# FT231X_Module.net
KiCad netlist of a schematic drawn in EAGLE
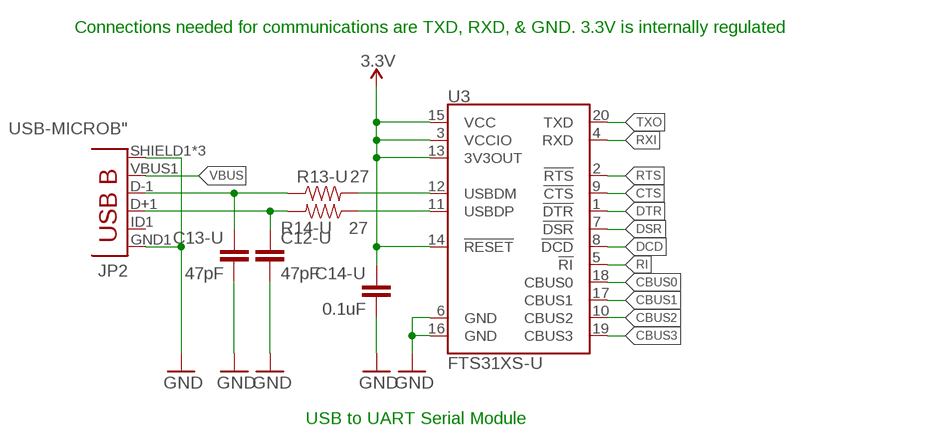
[diagram p0: schematic, sheet 1]

(export (version "E")
  (design (tool "Eeschema 10.0.6"))
  (components
    (comp (ref "C12-U")
      (value "47pF")
      (footprint "eagle-import:0603-CAP")
      (libsource (lib "eagle-import") (part "47PF-50V-5%(0603)"))
    )
    (comp (ref "C13-U")
      (value "47pF")
      (footprint "eagle-import:0603-CAP")
      (libsource (lib "eagle-import") (part "47PF-50V-5%(0603)"))
    )
    (comp (ref "C14-U")
      (value "0.1uF")
      (footprint "eagle-import:0603-CAP")
      (libsource (lib "eagle-import") (part "0.1UF-25V(+80/-20%)(0603)"))
    )
    (comp (ref "JP2")
      (value "USB-MICROB\"")
      (footprint "eagle-import:USB-B-MICRO-SMD_V03")
      (libsource (lib "eagle-import") (part "USB-MICROB{dblquote}"))
    )
    (comp (ref "R13-U")
      (value "27")
      (footprint "eagle-import:0603-RES")
      (libsource (lib "eagle-import") (part "27OHM1/10W1%(0603)0603-RES"))
    )
    (comp (ref "R14-U")
      (value "27")
      (footprint "eagle-import:0603-RES")
      (libsource (lib "eagle-import") (part "27OHM1/10W1%(0603)0603-RES"))
    )
    (comp (ref "U3")
      (value "FTS31XS-U")
      (footprint "eagle-import:SSOP20_L")
      (libsource (lib "eagle-import") (part "FT231XS"))
    )
  )
  (nets
    (net (code "1") (name "3.3V") (class "Default")
      (node (ref "C14-U") (pin "1") (pinfunction "1_1") (pintype "passive"))
      (node (ref "U3") (pin "13") (pinfunction "3V3OUT_13") (pintype "bidirectional"))
      (node (ref "U3") (pin "14") (pinfunction "~{RESET}_14") (pintype "bidirectional"))
      (node (ref "U3") (pin "15") (pinfunction "VCC_15") (pintype "bidirectional"))
      (node (ref "U3") (pin "3") (pinfunction "VCCIO_3") (pintype "bidirectional"))
    )
    (net (code "2") (name "CBUS0") (class "Default")
      (node (ref "U3") (pin "18") (pinfunction "CBUS0_18") (pintype "bidirectional"))
    )
    (net (code "3") (name "CBUS1") (class "Default")
      (node (ref "U3") (pin "17") (pinfunction "CBUS1_17") (pintype "bidirectional"))
    )
    (net (code "4") (name "CBUS2") (class "Default")
      (node (ref "U3") (pin "10") (pinfunction "CBUS2_10") (pintype "bidirectional"))
    )
    (net (code "5") (name "CBUS3") (class "Default")
      (node (ref "U3") (pin "19") (pinfunction "CBUS3_19") (pintype "bidirectional"))
    )
    (net (code "6") (name "CTS") (class "Default")
      (node (ref "U3") (pin "9") (pinfunction "~{CTS}_9") (pintype "bidirectional"))
    )
    (net (code "7") (name "DCD") (class "Default")
      (node (ref "U3") (pin "8") (pinfunction "~{DCD}_8") (pintype "bidirectional"))
    )
    (net (code "8") (name "DSR") (class "Default")
      (node (ref "U3") (pin "7") (pinfunction "~{DSR}_7") (pintype "bidirectional"))
    )
    (net (code "9") (name "DTR") (class "Default")
      (node (ref "U3") (pin "1") (pinfunction "~{DTR}_1") (pintype "bidirectional"))
    )
    (net (code "10") (name "GND") (class "Default")
      (node (ref "C12-U") (pin "2") (pinfunction "2_2") (pintype "passive"))
      (node (ref "C13-U") (pin "2") (pinfunction "2_2") (pintype "passive"))
      (node (ref "C14-U") (pin "2") (pinfunction "2_2") (pintype "passive"))
      (node (ref "JP2") (pin "GND1") (pinfunction "GND_GND1") (pintype "bidirectional"))
      (node (ref "JP2") (pin "SHIELD1") (pinfunction "SHIELD_SHIELD1") (pintype "bidirectional"))
      (node (ref "JP2") (pin "SHIELD2") (pinfunction "SHIELD_SHIELD2") (pintype "bidirectional"))
      (node (ref "JP2") (pin "SHIELD3") (pinfunction "SHIELD_SHIELD3") (pintype "bidirectional"))
      (node (ref "U3") (pin "16") (pinfunction "GND_16") (pintype "bidirectional"))
      (node (ref "U3") (pin "6") (pinfunction "GND_6") (pintype "bidirectional"))
    )
    (net (code "11") (name "Net-(JP2-D+)") (class "Default")
      (node (ref "C12-U") (pin "1") (pinfunction "1_1") (pintype "passive"))
      (node (ref "JP2") (pin "D+1") (pinfunction "D+_D+1") (pintype "bidirectional"))
      (node (ref "R14-U") (pin "2") (pinfunction "2_2") (pintype "passive"))
    )
    (net (code "12") (name "Net-(JP2-D-)") (class "Default")
      (node (ref "C13-U") (pin "1") (pinfunction "1_1") (pintype "passive"))
      (node (ref "JP2") (pin "D-1") (pinfunction "D-_D-1") (pintype "bidirectional"))
      (node (ref "R13-U") (pin "1") (pinfunction "1_1") (pintype "passive"))
    )
    (net (code "13") (name "Net-(U3-USBDM)") (class "Default")
      (node (ref "R13-U") (pin "2") (pinfunction "2_2") (pintype "passive"))
      (node (ref "U3") (pin "12") (pinfunction "USBDM_12") (pintype "bidirectional"))
    )
    (net (code "14") (name "Net-(U3-USBDP)") (class "Default")
      (node (ref "R14-U") (pin "1") (pinfunction "1_1") (pintype "passive"))
      (node (ref "U3") (pin "11") (pinfunction "USBDP_11") (pintype "bidirectional"))
    )
    (net (code "15") (name "RI") (class "Default")
      (node (ref "U3") (pin "5") (pinfunction "~{RI}_5") (pintype "bidirectional"))
    )
    (net (code "16") (name "RTS") (class "Default")
      (node (ref "U3") (pin "2") (pinfunction "~{RTS}_2") (pintype "bidirectional"))
    )
    (net (code "17") (name "RXI") (class "Default")
      (node (ref "U3") (pin "4") (pinfunction "RXD_4") (pintype "bidirectional"))
    )
    (net (code "18") (name "TXO") (class "Default")
      (node (ref "U3") (pin "20") (pinfunction "TXD_20") (pintype "bidirectional"))
    )
    (net (code "19") (name "VBUS") (class "Default")
      (node (ref "JP2") (pin "VBUS1") (pinfunction "VBUS_VBUS1") (pintype "bidirectional"))
    )
    (net (code "20") (name "unconnected-(JP2-USBID-PadID1)") (class "Default")
      (node (ref "JP2") (pin "ID1") (pinfunction "USBID_ID1") (pintype "bidirectional"))
    )
  )
)
